# Antenna_Matching_Circuit.net
KiCad netlist of a schematic drawn in Altium Designer
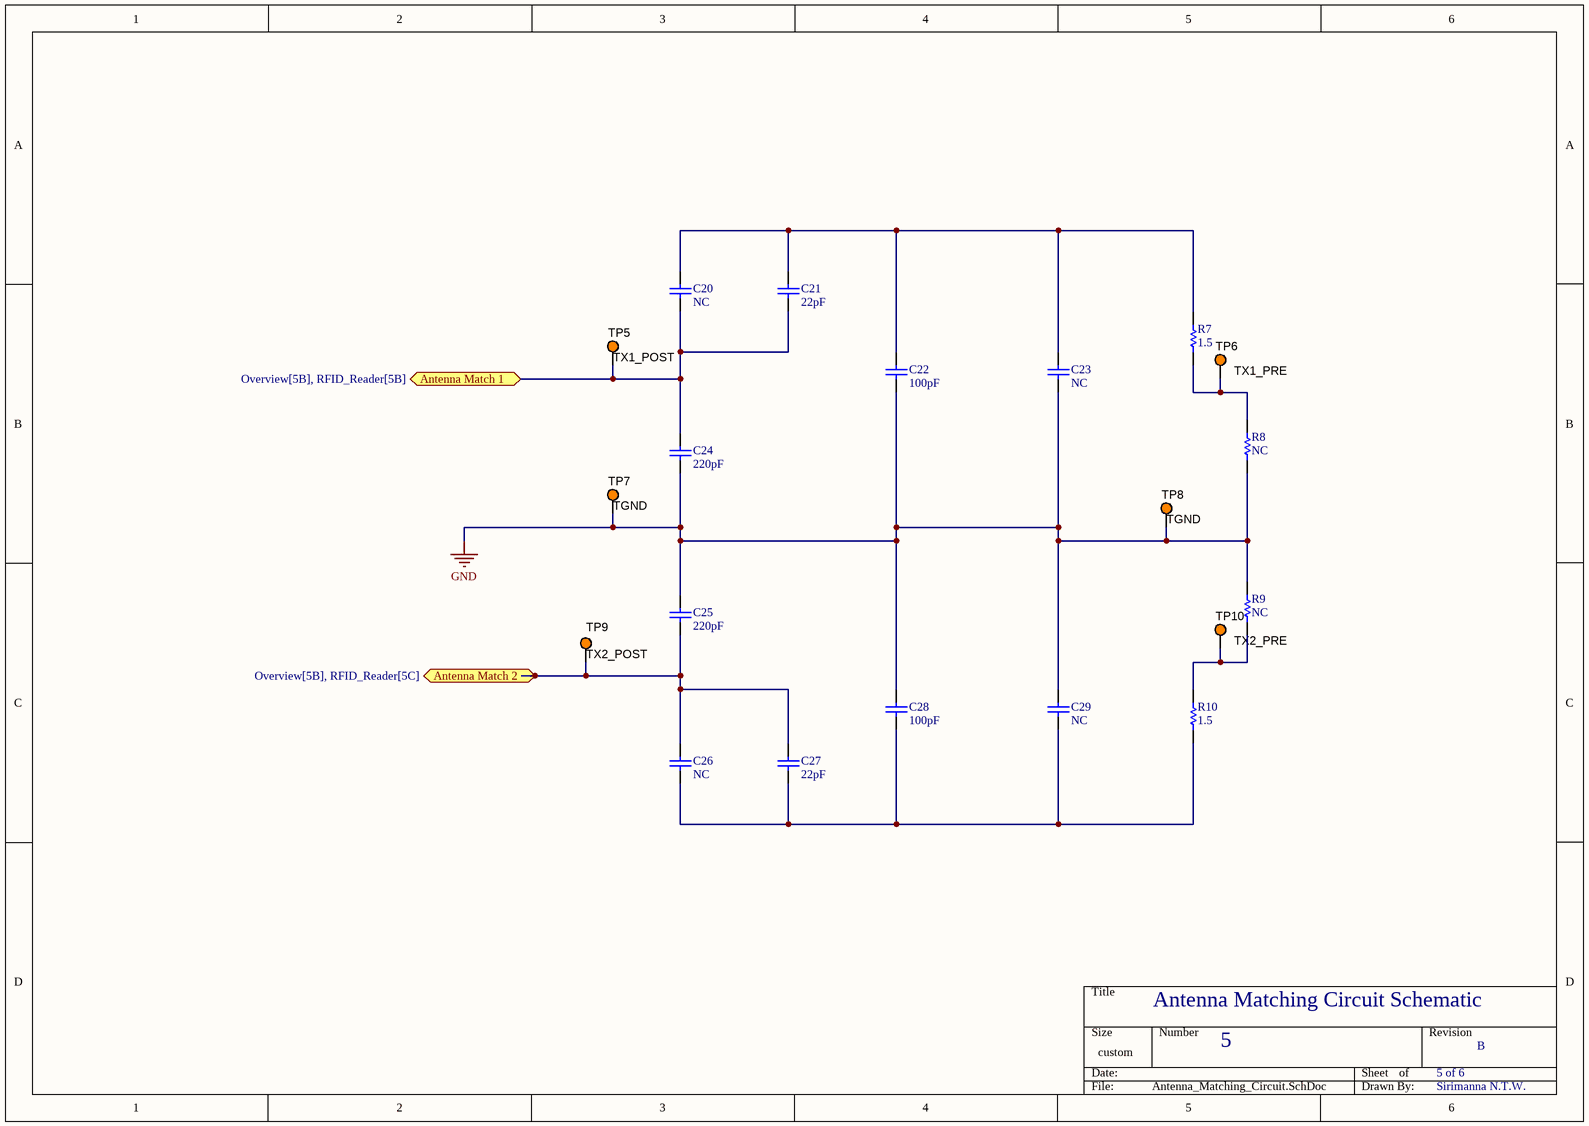
[diagram p0: Antenna_Matching_Circuit.SchDoc]

(export (version "E")
  (design (tool "Eeschema 10.0.6"))
  (components
    (comp (ref "C20")
      (value "NC")
      (footprint "CAPC2013X135X45NL10T25")
      (description "Chip Capacitor, 0.1 uF, +/- 10%, 50 V, -55 to 125 degC, 0805 (2012 Metric), RoHS, Tape and Reel")
      (fields (field (name "VOLTAGE") "50V") (field (name "TOLERANCE") "10%"))
      (libsource (lib "Altium Content Vault") (part "CAP-NP-2"))
    )
    (comp (ref "C21")
      (value "22pF")
      (footprint "CAPC2013X135X45NL10T25")
      (description "Chip Capacitor, 0.1 uF, +/- 10%, 50 V, -55 to 125 degC, 0805 (2012 Metric), RoHS, Tape and Reel")
      (fields (field (name "VOLTAGE") "50V") (field (name "TOLERANCE") "10%"))
      (libsource (lib "Altium Content Vault") (part "CAP-NP-2"))
    )
    (comp (ref "C22")
      (value "100pF")
      (footprint "CAPC2013X135X45NL10T25")
      (description "Chip Capacitor, 0.1 uF, +/- 10%, 50 V, -55 to 125 degC, 0805 (2012 Metric), RoHS, Tape and Reel")
      (fields (field (name "VOLTAGE") "50V") (field (name "TOLERANCE") "10%"))
      (libsource (lib "Altium Content Vault") (part "CAP-NP-2"))
    )
    (comp (ref "C23")
      (value "NC")
      (footprint "CAPC2013X135X45NL10T25")
      (description "Chip Capacitor, 0.1 uF, +/- 10%, 50 V, -55 to 125 degC, 0805 (2012 Metric), RoHS, Tape and Reel")
      (fields (field (name "VOLTAGE") "50V") (field (name "TOLERANCE") "10%"))
      (libsource (lib "Altium Content Vault") (part "CAP-NP-2"))
    )
    (comp (ref "C24")
      (value "220pF")
      (footprint "CAPC2013X135X45NL10T25")
      (description "Chip Capacitor, 0.1 uF, +/- 10%, 50 V, -55 to 125 degC, 0805 (2012 Metric), RoHS, Tape and Reel")
      (fields (field (name "VOLTAGE") "50V") (field (name "TOLERANCE") "10%"))
      (libsource (lib "Altium Content Vault") (part "CAP-NP-2"))
    )
    (comp (ref "C25")
      (value "220pF")
      (footprint "CAPC2013X135X45NL10T25")
      (description "Chip Capacitor, 0.1 uF, +/- 10%, 50 V, -55 to 125 degC, 0805 (2012 Metric), RoHS, Tape and Reel")
      (fields (field (name "VOLTAGE") "50V") (field (name "TOLERANCE") "10%"))
      (libsource (lib "Altium Content Vault") (part "CAP-NP-2"))
    )
    (comp (ref "C26")
      (value "NC")
      (footprint "CAPC2013X135X45NL10T25")
      (description "Chip Capacitor, 0.1 uF, +/- 10%, 50 V, -55 to 125 degC, 0805 (2012 Metric), RoHS, Tape and Reel")
      (fields (field (name "VOLTAGE") "50V") (field (name "TOLERANCE") "10%"))
      (libsource (lib "Altium Content Vault") (part "CAP-NP-2"))
    )
    (comp (ref "C27")
      (value "22pF")
      (footprint "CAPC2013X135X45NL10T25")
      (description "Chip Capacitor, 0.1 uF, +/- 10%, 50 V, -55 to 125 degC, 0805 (2012 Metric), RoHS, Tape and Reel")
      (fields (field (name "VOLTAGE") "50V") (field (name "TOLERANCE") "10%"))
      (libsource (lib "Altium Content Vault") (part "CAP-NP-2"))
    )
    (comp (ref "C28")
      (value "100pF")
      (footprint "CAPC2013X135X45NL10T25")
      (description "Chip Capacitor, 0.1 uF, +/- 10%, 50 V, -55 to 125 degC, 0805 (2012 Metric), RoHS, Tape and Reel")
      (fields (field (name "VOLTAGE") "50V") (field (name "TOLERANCE") "10%"))
      (libsource (lib "Altium Content Vault") (part "CAP-NP-2"))
    )
    (comp (ref "C29")
      (value "NC")
      (footprint "CAPC2013X135X45NL10T25")
      (description "Chip Capacitor, 0.1 uF, +/- 10%, 50 V, -55 to 125 degC, 0805 (2012 Metric), RoHS, Tape and Reel")
      (fields (field (name "VOLTAGE") "50V") (field (name "TOLERANCE") "10%"))
      (libsource (lib "Altium Content Vault") (part "CAP-NP-2"))
    )
    (comp (ref "R7")
      (value "1.5")
      (footprint "RESC2013X70X40NL20T20")
      (fields (field (name "PART NUMBER") "ERJ6BQF1R5V") (field (name "MANUFACTURER") "Panasonic"))
      (libsource (lib "Altium Content Vault") (part "RES"))
    )
    (comp (ref "R8")
      (value "NC")
      (footprint "RESC1005X40X25NL05T05")
      (fields (field (name "MANUFACTURER") "Vishay Dale") (field (name "PART NUMBER") "CRCW040222R0FKED"))
      (libsource (lib "Altium Content Vault") (part "RES"))
    )
    (comp (ref "R9")
      (value "NC")
      (footprint "RESC1005X40X25LL05T05")
      (fields (field (name "MANUFACTURER") "Vishay Dale") (field (name "PART NUMBER") "CRCW040222R0FKED"))
      (libsource (lib "Altium Content Vault") (part "RES"))
    )
    (comp (ref "R10")
      (value "1.5")
      (footprint "RESC2013X70X40NL20T20")
      (fields (field (name "PART NUMBER") "ERJ6BQF1R5V") (field (name "MANUFACTURER") "Panasonic"))
      (libsource (lib "Altium Content Vault") (part "RES"))
    )
    (comp (ref "TP5")
      (value "TX1_POST")
      (footprint "KSTN-5003")
      (description "Test Point, Orange, 1-Pin THD, RoHS")
      (libsource (lib "Altium Content Vault") (part "TESTPOINT_ORANGE"))
    )
    (comp (ref "TP6")
      (value "TX1_PRE")
      (footprint "KSTN-5003")
      (description "Test Point, Orange, 1-Pin THD, RoHS")
      (libsource (lib "Altium Content Vault") (part "TESTPOINT_ORANGE"))
    )
    (comp (ref "TP7")
      (value "TGND")
      (footprint "KSTN-5003")
      (description "Test Point, Orange, 1-Pin THD, RoHS")
      (libsource (lib "Altium Content Vault") (part "TESTPOINT_ORANGE"))
    )
    (comp (ref "TP8")
      (value "TGND")
      (footprint "KSTN-5003")
      (description "Test Point, Orange, 1-Pin THD, RoHS")
      (libsource (lib "Altium Content Vault") (part "TESTPOINT_ORANGE"))
    )
    (comp (ref "TP9")
      (value "TX2_POST")
      (footprint "KSTN-5003")
      (description "Test Point, Orange, 1-Pin THD, RoHS")
      (libsource (lib "Altium Content Vault") (part "TESTPOINT_ORANGE"))
    )
    (comp (ref "TP10")
      (value "TX2_PRE")
      (footprint "KSTN-5003")
      (description "Test Point, Orange, 1-Pin THD, RoHS")
      (libsource (lib "Altium Content Vault") (part "TESTPOINT_ORANGE"))
    )
  )
  (nets
    (net (code "1") (name "/Antenna Match 1") (class "Default")
      (node (ref "C20") (pin "1") (pinfunction "1_1") (pintype "passive"))
      (node (ref "C21") (pin "1") (pinfunction "1_1") (pintype "passive"))
      (node (ref "C24") (pin "2") (pinfunction "2_2") (pintype "passive"))
      (node (ref "TP5") (pin "1") (pinfunction "1_1") (pintype "passive"))
    )
    (net (code "2") (name "/Antenna Match 2") (class "Default")
      (node (ref "C25") (pin "1") (pinfunction "1_1") (pintype "passive"))
      (node (ref "C26") (pin "2") (pinfunction "2_2") (pintype "passive"))
      (node (ref "C27") (pin "2") (pinfunction "2_2") (pintype "passive"))
      (node (ref "TP9") (pin "1") (pinfunction "1_1") (pintype "passive"))
    )
    (net (code "3") (name "GND") (class "Default")
      (node (ref "C22") (pin "1") (pinfunction "1_1") (pintype "passive"))
      (node (ref "C23") (pin "1") (pinfunction "1_1") (pintype "passive"))
      (node (ref "C24") (pin "1") (pinfunction "1_1") (pintype "passive"))
      (node (ref "C25") (pin "2") (pinfunction "2_2") (pintype "passive"))
      (node (ref "C28") (pin "2") (pinfunction "2_2") (pintype "passive"))
      (node (ref "C29") (pin "2") (pinfunction "2_2") (pintype "passive"))
      (node (ref "R8") (pin "2") (pinfunction "2_2") (pintype "passive"))
      (node (ref "R9") (pin "1") (pinfunction "1_1") (pintype "passive"))
      (node (ref "TP7") (pin "1") (pinfunction "1_1") (pintype "passive"))
      (node (ref "TP8") (pin "1") (pinfunction "1_1") (pintype "passive"))
    )
    (net (code "4") (name "Net-(C20-Pad2)") (class "Default")
      (node (ref "C20") (pin "2") (pinfunction "2_2") (pintype "passive"))
      (node (ref "C21") (pin "2") (pinfunction "2_2") (pintype "passive"))
      (node (ref "C22") (pin "2") (pinfunction "2_2") (pintype "passive"))
      (node (ref "C23") (pin "2") (pinfunction "2_2") (pintype "passive"))
      (node (ref "R7") (pin "1") (pinfunction "1_1") (pintype "passive"))
    )
    (net (code "5") (name "Net-(C26-Pad1)") (class "Default")
      (node (ref "C26") (pin "1") (pinfunction "1_1") (pintype "passive"))
      (node (ref "C27") (pin "1") (pinfunction "1_1") (pintype "passive"))
      (node (ref "C28") (pin "1") (pinfunction "1_1") (pintype "passive"))
      (node (ref "C29") (pin "1") (pinfunction "1_1") (pintype "passive"))
      (node (ref "R10") (pin "2") (pinfunction "2_2") (pintype "passive"))
    )
    (net (code "6") (name "Net-(R7-Pad2)") (class "Default")
      (node (ref "R7") (pin "2") (pinfunction "2_2") (pintype "passive"))
      (node (ref "R8") (pin "1") (pinfunction "1_1") (pintype "passive"))
      (node (ref "TP6") (pin "1") (pinfunction "1_1") (pintype "passive"))
    )
    (net (code "7") (name "Net-(R10-Pad1)") (class "Default")
      (node (ref "R10") (pin "1") (pinfunction "1_1") (pintype "passive"))
      (node (ref "R9") (pin "2") (pinfunction "2_2") (pintype "passive"))
      (node (ref "TP10") (pin "1") (pinfunction "1_1") (pintype "passive"))
    )
  )
)
